# AGC-Amplifier-LM13600-Stereo.net
KiCad netlist of a schematic drawn in EAGLE
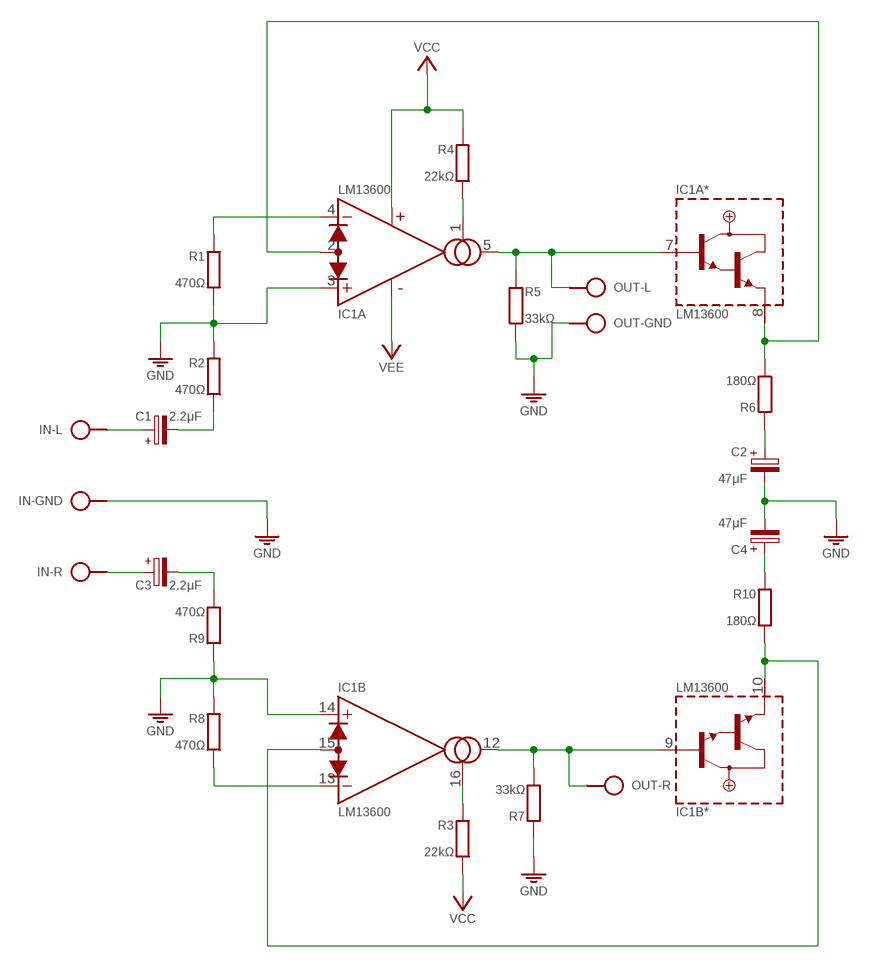
[diagram p0: schematic, sheet 1]

(export (version "E")
  (design (tool "Eeschema 10.0.6"))
  (components
    (comp (ref "C1")
      (value "2.2μF")
      (footprint "eagle-import:E2,5-4")
      (libsource (lib "eagle-import") (part "CPOL-HE2,5-4"))
    )
    (comp (ref "C2")
      (value "47μF")
      (footprint "eagle-import:E2.5-4_V")
      (libsource (lib "eagle-import") (part "CPOLE2,5-4/V"))
    )
    (comp (ref "C3")
      (value "2.2μF")
      (footprint "eagle-import:E2,5-4")
      (libsource (lib "eagle-import") (part "CPOL-HE2,5-4"))
    )
    (comp (ref "C4")
      (value "47μF")
      (footprint "eagle-import:E2.5-4_V")
      (libsource (lib "eagle-import") (part "CPOLE2,5-4/V"))
    )
    (comp (ref "IC1")
      (value "LM13600")
      (footprint "eagle-import:DIL16")
      (libsource (lib "eagle-import") (part "LM13600"))
    )
    (comp (ref "IN")
      (value "SAUDIOL-GND-R")
      (footprint "eagle-import:SPAD-L-GND-R")
      (libsource (lib "eagle-import") (part "SAUDIOL-GND-R"))
    )
    (comp (ref "OUT")
      (value "SAUDIO")
      (footprint "eagle-import:SPAD-3")
      (libsource (lib "eagle-import") (part "SAUDIO"))
    )
    (comp (ref "PWR")
      (value "VCC_GND_VEEPWR--GND+")
      (footprint "eagle-import:SPAD-PWR--GND+")
      (libsource (lib "eagle-import") (part "VCC_GND_VEEPWR--GND+"))
    )
    (comp (ref "R1")
      (value "470Ω")
      (footprint "eagle-import:0202_7-V")
      (libsource (lib "eagle-import") (part "R0202/7-V"))
    )
    (comp (ref "R2")
      (value "470Ω")
      (footprint "eagle-import:0202_7")
      (libsource (lib "eagle-import") (part "R0202/7"))
    )
    (comp (ref "R3")
      (value "22kΩ")
      (footprint "eagle-import:0202_7")
      (libsource (lib "eagle-import") (part "R0202/7"))
    )
    (comp (ref "R4")
      (value "22kΩ")
      (footprint "eagle-import:0202_7")
      (libsource (lib "eagle-import") (part "R0202/7"))
    )
    (comp (ref "R5")
      (value "33kΩ")
      (footprint "eagle-import:0202_7-V")
      (libsource (lib "eagle-import") (part "R0202/7-V"))
    )
    (comp (ref "R6")
      (value "180Ω")
      (footprint "eagle-import:0202_7-V")
      (libsource (lib "eagle-import") (part "R0202/7-V"))
    )
    (comp (ref "R7")
      (value "33kΩ")
      (footprint "eagle-import:0202_7-V")
      (libsource (lib "eagle-import") (part "R0202/7-V"))
    )
    (comp (ref "R8")
      (value "470Ω")
      (footprint "eagle-import:0202_7-V")
      (libsource (lib "eagle-import") (part "R0202/7-V"))
    )
    (comp (ref "R9")
      (value "470Ω")
      (footprint "eagle-import:0202_7-V")
      (libsource (lib "eagle-import") (part "R0202/7-V"))
    )
    (comp (ref "R10")
      (value "180Ω")
      (footprint "eagle-import:0202_7-V")
      (libsource (lib "eagle-import") (part "R0202/7-V"))
    )
  )
  (nets
    (net (code "1") (name "GND") (class "Default")
      (node (ref "C2") (pin "-") (pinfunction "-_-") (pintype "passive"))
      (node (ref "C4") (pin "-") (pinfunction "-_-") (pintype "passive"))
      (node (ref "IC1") (pin "14") (pinfunction "+IN_14") (pintype "input"))
      (node (ref "IC1") (pin "3") (pinfunction "+IN_3") (pintype "input"))
      (node (ref "IN") (pin "0") (pinfunction "P$1_0") (pintype "passive"))
      (node (ref "OUT") (pin "2") (pinfunction "P$1_2") (pintype "passive"))
      (node (ref "PWR") (pin "GND") (pinfunction "GND_GND") (pintype "power_in"))
      (node (ref "R1") (pin "2") (pinfunction "2_2") (pintype "passive"))
      (node (ref "R2") (pin "1") (pinfunction "1_1") (pintype "passive"))
      (node (ref "R5") (pin "2") (pinfunction "2_2") (pintype "passive"))
      (node (ref "R7") (pin "1") (pinfunction "1_1") (pintype "passive"))
      (node (ref "R8") (pin "1") (pinfunction "1_1") (pintype "passive"))
      (node (ref "R9") (pin "1") (pinfunction "1_1") (pintype "passive"))
    )
    (net (code "2") (name "Net-(C1-Pad-)") (class "Default")
      (node (ref "C1") (pin "-") (pinfunction "-_-") (pintype "passive"))
      (node (ref "R2") (pin "2") (pinfunction "2_2") (pintype "passive"))
    )
    (net (code "3") (name "Net-(C2-Pad+)") (class "Default")
      (node (ref "C2") (pin "+") (pinfunction "+_+") (pintype "passive"))
      (node (ref "R6") (pin "1") (pinfunction "1_1") (pintype "passive"))
    )
    (net (code "4") (name "Net-(C3-Pad-)") (class "Default")
      (node (ref "C3") (pin "-") (pinfunction "-_-") (pintype "passive"))
      (node (ref "R9") (pin "2") (pinfunction "2_2") (pintype "passive"))
    )
    (net (code "5") (name "Net-(C4-Pad+)") (class "Default")
      (node (ref "C4") (pin "+") (pinfunction "+_+") (pintype "passive"))
      (node (ref "R10") (pin "1") (pinfunction "1_1") (pintype "passive"))
    )
    (net (code "6") (name "Net-(IC1A-V-)") (class "Default")
      (node (ref "IC1") (pin "6") (pinfunction "V-_6") (pintype "power_in"))
      (node (ref "PWR") (pin "VEE") (pinfunction "VEE_VEE") (pintype "power_in"))
    )
    (net (code "7") (name "Net-(IC1B--IN)") (class "Default")
      (node (ref "IC1") (pin "4") (pinfunction "-IN_4") (pintype "input"))
      (node (ref "R1") (pin "1") (pinfunction "1_1") (pintype "passive"))
    )
    (net (code "8") (name "Net-(IC1B-AMP{slash}BIAS)") (class "Default")
      (node (ref "IC1") (pin "1") (pinfunction "AMP/BIAS_1") (pintype "input"))
      (node (ref "R4") (pin "2") (pinfunction "2_2") (pintype "passive"))
    )
    (net (code "9") (name "Net-(IC1B-DIODE{slash}BIAS)") (class "Default")
      (node (ref "IC1") (pin "2") (pinfunction "DIODE/BIAS_2") (pintype "passive"))
      (node (ref "IC1") (pin "8") (pinfunction "BUFF/OUT_8") (pintype "output"))
      (node (ref "R6") (pin "2") (pinfunction "2_2") (pintype "passive"))
    )
    (net (code "10") (name "Net-(IC1B-OUT)") (class "Default")
      (node (ref "IC1") (pin "5") (pinfunction "OUT_5") (pintype "output"))
      (node (ref "IC1") (pin "7") (pinfunction "BUFF/IN_7") (pintype "input"))
      (node (ref "OUT") (pin "1") (pinfunction "P$1_1") (pintype "passive"))
      (node (ref "R5") (pin "1") (pinfunction "1_1") (pintype "passive"))
    )
    (net (code "11") (name "Net-(IC1D--IN)") (class "Default")
      (node (ref "IC1") (pin "13") (pinfunction "-IN_13") (pintype "input"))
      (node (ref "R8") (pin "2") (pinfunction "2_2") (pintype "passive"))
    )
    (net (code "12") (name "Net-(IC1D-AMP{slash}BIAS)") (class "Default")
      (node (ref "IC1") (pin "16") (pinfunction "AMP/BIAS_16") (pintype "input"))
      (node (ref "R3") (pin "1") (pinfunction "1_1") (pintype "passive"))
    )
    (net (code "13") (name "Net-(IC1D-DIODE{slash}BIAS)") (class "Default")
      (node (ref "IC1") (pin "10") (pinfunction "BUFF/OUT_10") (pintype "output"))
      (node (ref "IC1") (pin "15") (pinfunction "DIODE/BIAS_15") (pintype "passive"))
      (node (ref "R10") (pin "2") (pinfunction "2_2") (pintype "passive"))
    )
    (net (code "14") (name "Net-(IC1D-OUT)") (class "Default")
      (node (ref "IC1") (pin "12") (pinfunction "OUT_12") (pintype "output"))
      (node (ref "IC1") (pin "9") (pinfunction "BUFF/IN_9") (pintype "input"))
      (node (ref "OUT") (pin "3") (pinfunction "P$1_3") (pintype "passive"))
      (node (ref "R7") (pin "2") (pinfunction "2_2") (pintype "passive"))
    )
    (net (code "15") (name "Net-(INB-P$1)") (class "Default")
      (node (ref "C1") (pin "+") (pinfunction "+_+") (pintype "passive"))
      (node (ref "IN") (pin "L") (pinfunction "P$1_L") (pintype "passive"))
    )
    (net (code "16") (name "Net-(INC-P$1)") (class "Default")
      (node (ref "C3") (pin "+") (pinfunction "+_+") (pintype "passive"))
      (node (ref "IN") (pin "R") (pinfunction "P$1_R") (pintype "passive"))
    )
    (net (code "17") (name "VCC") (class "Default")
      (node (ref "IC1") (pin "11") (pinfunction "V+_11") (pintype "power_in"))
      (node (ref "PWR") (pin "VCC") (pinfunction "VCC_VCC") (pintype "power_in"))
      (node (ref "R3") (pin "2") (pinfunction "2_2") (pintype "passive"))
      (node (ref "R4") (pin "1") (pinfunction "1_1") (pintype "passive"))
    )
  )
)
